# main_board.net
KiCad netlist of a schematic drawn in EAGLE
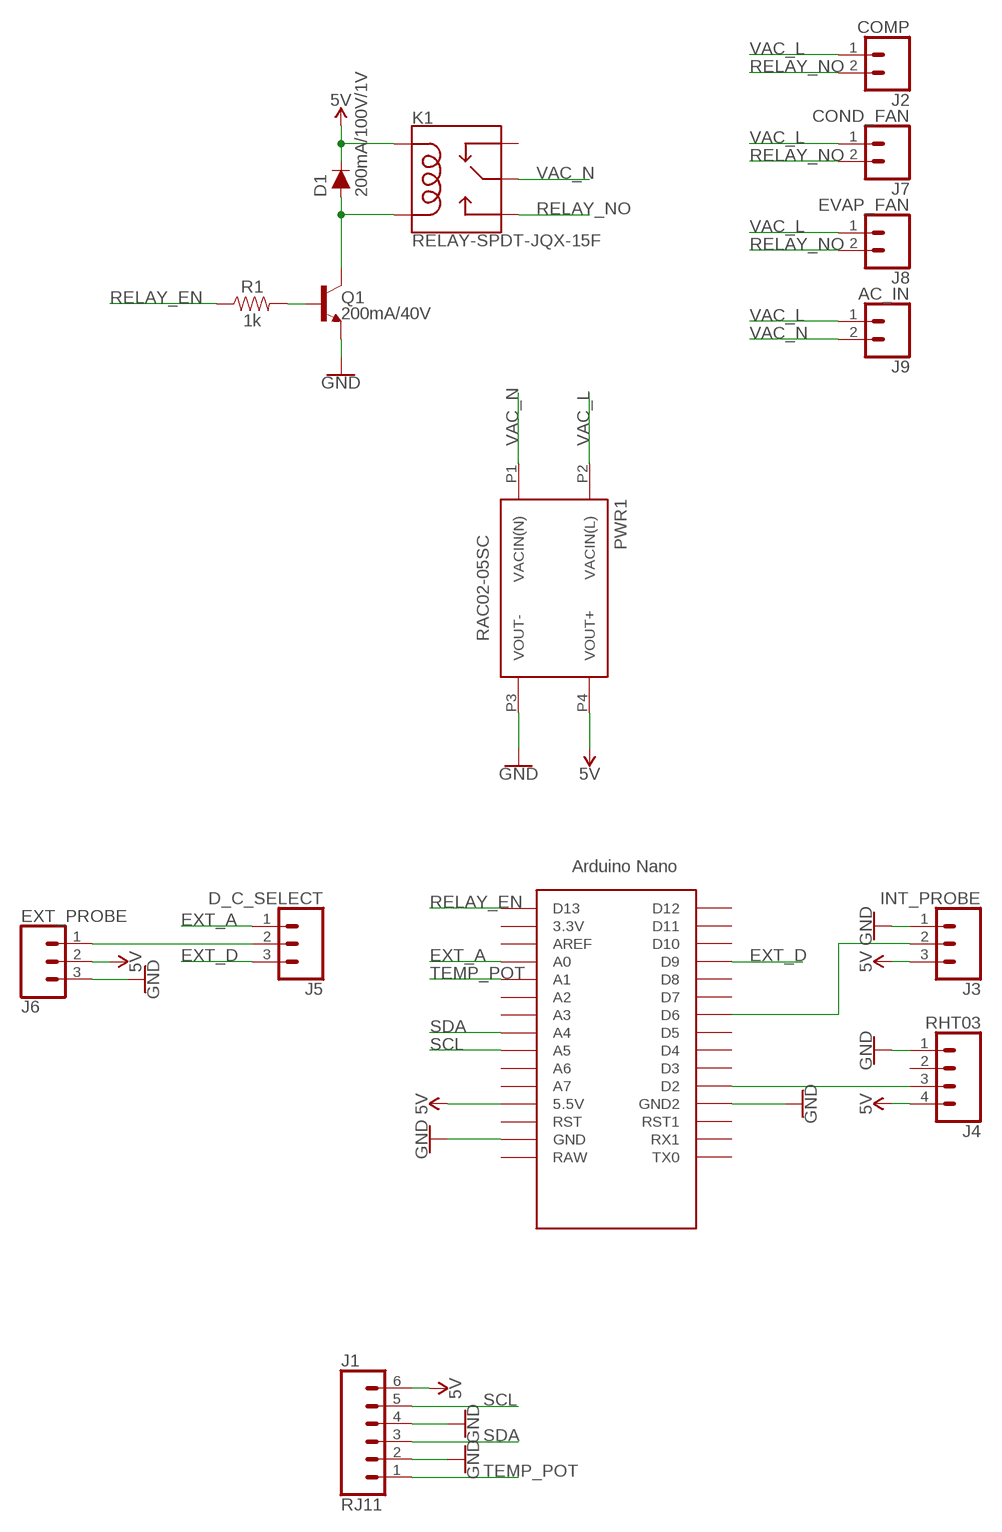
[diagram p0: schematic, sheet 1]

(export (version "E")
  (design (tool "Eeschema 10.0.6"))
  (components
    (comp (ref "D1")
      (value "200mA/100V/1V")
      (footprint "eagle-import:DIODE-1N4148")
      (libsource (lib "eagle-import") (part "DIODE-1N4148"))
    )
    (comp (ref "J1")
      (value "RJ11")
      (footprint "eagle-import:RJ11-6")
      (libsource (lib "eagle-import") (part "RJ11-6"))
    )
    (comp (ref "J2")
      (value "COMP")
      (footprint "eagle-import:SCREWTERMINAL-5MM-2")
      (libsource (lib "eagle-import") (part "CONN_025MM"))
    )
    (comp (ref "J3")
      (value "INT_PROBE")
      (footprint "eagle-import:1X03")
      (libsource (lib "eagle-import") (part "CONN_03"))
    )
    (comp (ref "J4")
      (value "RHT03")
      (footprint "eagle-import:1X04")
      (libsource (lib "eagle-import") (part "CONN_04"))
    )
    (comp (ref "J5")
      (value "D_C_SELECT")
      (footprint "eagle-import:1X03")
      (libsource (lib "eagle-import") (part "CONN_03"))
    )
    (comp (ref "J6")
      (value "EXT_PROBE")
      (footprint "eagle-import:1X03")
      (libsource (lib "eagle-import") (part "CONN_03"))
    )
    (comp (ref "J7")
      (value "COND_FAN")
      (footprint "eagle-import:SCREWTERMINAL-5MM-2")
      (libsource (lib "eagle-import") (part "CONN_025MM"))
    )
    (comp (ref "J8")
      (value "EVAP_FAN")
      (footprint "eagle-import:SCREWTERMINAL-5MM-2")
      (libsource (lib "eagle-import") (part "CONN_025MM"))
    )
    (comp (ref "J9")
      (value "AC_IN")
      (footprint "eagle-import:SCREWTERMINAL-5MM-2")
      (libsource (lib "eagle-import") (part "CONN_025MM"))
    )
    (comp (ref "K1")
      (value "RELAY-SPDT-JQX-15F")
      (footprint "eagle-import:RELAY-T90")
      (libsource (lib "eagle-import") (part "RELAY-SPDT-JQX-15F"))
    )
    (comp (ref "PWR1")
      (value "RAC02-05SC")
      (footprint "eagle-import:LOW_PROFILE_POWER_MODULE")
      (libsource (lib "eagle-import") (part "RACSC02-05"))
    )
    (comp (ref "Q1")
      (value "200mA/40V")
      (footprint "eagle-import:TO-92")
      (libsource (lib "eagle-import") (part "TRANS_NPN-2N3904"))
    )
    (comp (ref "R1")
      (value "1k")
      (footprint "eagle-import:AXIAL-0.3")
      (libsource (lib "eagle-import") (part "1KOHM-HORIZ-1/4W-1%"))
    )
    (comp (ref "U$1")
      (value "NANO")
      (footprint "eagle-import:NANO")
      (libsource (lib "eagle-import") (part "NANO"))
    )
  )
  (nets
    (net (code "1") (name "/EXT_A") (class "Default")
      (node (ref "J5") (pin "1") (pinfunction "1_1") (pintype "passive"))
      (node (ref "U$1") (pin "A0") (pinfunction "A0_A0") (pintype "bidirectional"))
    )
    (net (code "2") (name "/EXT_D") (class "Default")
      (node (ref "J5") (pin "3") (pinfunction "3_3") (pintype "passive"))
      (node (ref "U$1") (pin "D9") (pinfunction "D9_D9") (pintype "bidirectional"))
    )
    (net (code "3") (name "/RELAY_EN") (class "Default")
      (node (ref "R1") (pin "P$1") (pinfunction "1_P$1") (pintype "passive"))
      (node (ref "U$1") (pin "D13") (pinfunction "D13_D13") (pintype "bidirectional"))
    )
    (net (code "4") (name "/RELAY_NO") (class "Default")
      (node (ref "J2") (pin "2") (pinfunction "2_2") (pintype "passive"))
      (node (ref "J7") (pin "2") (pinfunction "2_2") (pintype "passive"))
      (node (ref "J8") (pin "2") (pinfunction "2_2") (pintype "passive"))
      (node (ref "K1") (pin "NO") (pinfunction "NO_NO") (pintype "bidirectional"))
    )
    (net (code "5") (name "/SCL") (class "Default")
      (node (ref "J1") (pin "5") (pinfunction "5_5") (pintype "passive"))
      (node (ref "U$1") (pin "A5") (pinfunction "A5_A5") (pintype "bidirectional"))
    )
    (net (code "6") (name "/SDA") (class "Default")
      (node (ref "J1") (pin "3") (pinfunction "3_3") (pintype "passive"))
      (node (ref "U$1") (pin "A4") (pinfunction "A4_A4") (pintype "bidirectional"))
    )
    (net (code "7") (name "/TEMP_POT") (class "Default")
      (node (ref "J1") (pin "1") (pinfunction "1_1") (pintype "passive"))
      (node (ref "U$1") (pin "A1") (pinfunction "A1_A1") (pintype "bidirectional"))
    )
    (net (code "8") (name "/VAC_L") (class "Default")
      (node (ref "J2") (pin "1") (pinfunction "1_1") (pintype "passive"))
      (node (ref "J7") (pin "1") (pinfunction "1_1") (pintype "passive"))
      (node (ref "J8") (pin "1") (pinfunction "1_1") (pintype "passive"))
      (node (ref "J9") (pin "1") (pinfunction "1_1") (pintype "passive"))
      (node (ref "PWR1") (pin "P2") (pinfunction "VACIN(L)_P2") (pintype "power_in"))
    )
    (net (code "9") (name "/VAC_N") (class "Default")
      (node (ref "J9") (pin "2") (pinfunction "2_2") (pintype "passive"))
      (node (ref "K1") (pin "MAIN") (pinfunction "MAIN_MAIN") (pintype "bidirectional"))
      (node (ref "PWR1") (pin "P1") (pinfunction "VACIN(N)_P1") (pintype "power_in"))
    )
    (net (code "10") (name "5V") (class "Default")
      (node (ref "D1") (pin "C") (pinfunction "C_C") (pintype "passive"))
      (node (ref "J1") (pin "6") (pinfunction "6_6") (pintype "passive"))
      (node (ref "J3") (pin "3") (pinfunction "3_3") (pintype "passive"))
      (node (ref "J4") (pin "4") (pinfunction "4_4") (pintype "passive"))
      (node (ref "J6") (pin "2") (pinfunction "2_2") (pintype "passive"))
      (node (ref "K1") (pin "COIL1") (pinfunction "COIL1_COIL1") (pintype "bidirectional"))
      (node (ref "PWR1") (pin "P4") (pinfunction "VOUT+_P4") (pintype "power_in"))
      (node (ref "U$1") (pin "5V") (pinfunction "5.5V_5V") (pintype "bidirectional"))
    )
    (net (code "11") (name "GND") (class "Default")
      (node (ref "J1") (pin "2") (pinfunction "2_2") (pintype "passive"))
      (node (ref "J1") (pin "4") (pinfunction "4_4") (pintype "passive"))
      (node (ref "J3") (pin "1") (pinfunction "1_1") (pintype "passive"))
      (node (ref "J4") (pin "1") (pinfunction "1_1") (pintype "passive"))
      (node (ref "J6") (pin "3") (pinfunction "3_3") (pintype "passive"))
      (node (ref "PWR1") (pin "P3") (pinfunction "VOUT-_P3") (pintype "power_in"))
      (node (ref "Q1") (pin "1") (pinfunction "E_1") (pintype "passive"))
      (node (ref "U$1") (pin "GND") (pinfunction "GND_GND") (pintype "bidirectional"))
      (node (ref "U$1") (pin "GND1") (pinfunction "GND2_GND1") (pintype "bidirectional"))
    )
    (net (code "12") (name "Net-(J3-Pad2)") (class "Default")
      (node (ref "J3") (pin "2") (pinfunction "2_2") (pintype "passive"))
      (node (ref "U$1") (pin "D6") (pinfunction "D6_D6") (pintype "bidirectional"))
    )
    (net (code "13") (name "Net-(J4-Pad3)") (class "Default")
      (node (ref "J4") (pin "3") (pinfunction "3_3") (pintype "passive"))
      (node (ref "U$1") (pin "D2") (pinfunction "D2_D2") (pintype "bidirectional"))
    )
    (net (code "14") (name "Net-(J5-Pad2)") (class "Default")
      (node (ref "J5") (pin "2") (pinfunction "2_2") (pintype "passive"))
      (node (ref "J6") (pin "1") (pinfunction "1_1") (pintype "passive"))
    )
    (net (code "15") (name "Net-(Q1-B)") (class "Default")
      (node (ref "Q1") (pin "2") (pinfunction "B_2") (pintype "passive"))
      (node (ref "R1") (pin "P$2") (pinfunction "2_P$2") (pintype "passive"))
    )
    (net (code "16") (name "Net-(Q1-C)") (class "Default")
      (node (ref "D1") (pin "A") (pinfunction "A_A") (pintype "passive"))
      (node (ref "K1") (pin "COIL2") (pinfunction "COIL2_COIL2") (pintype "bidirectional"))
      (node (ref "Q1") (pin "3") (pinfunction "C_3") (pintype "passive"))
    )
    (net (code "17") (name "unconnected-(J4-Pad2)") (class "Default")
      (node (ref "J4") (pin "2") (pinfunction "2_2") (pintype "passive"))
    )
    (net (code "18") (name "unconnected-(K1-PadNC)") (class "Default")
      (node (ref "K1") (pin "NC") (pinfunction "NC_NC") (pintype "bidirectional"))
    )
    (net (code "19") (name "unconnected-(U$1-Pad3.3V)") (class "Default")
      (node (ref "U$1") (pin "3.3V") (pinfunction "3.3V_3.3V") (pintype "bidirectional"))
    )
    (net (code "20") (name "unconnected-(U$1-PadA2)") (class "Default")
      (node (ref "U$1") (pin "A2") (pinfunction "A2_A2") (pintype "bidirectional"))
    )
    (net (code "21") (name "unconnected-(U$1-PadA3)") (class "Default")
      (node (ref "U$1") (pin "A3") (pinfunction "A3_A3") (pintype "bidirectional"))
    )
    (net (code "22") (name "unconnected-(U$1-PadA6)") (class "Default")
      (node (ref "U$1") (pin "A6") (pinfunction "A6_A6") (pintype "bidirectional"))
    )
    (net (code "23") (name "unconnected-(U$1-PadA7)") (class "Default")
      (node (ref "U$1") (pin "A7") (pinfunction "A7_A7") (pintype "bidirectional"))
    )
    (net (code "24") (name "unconnected-(U$1-PadAREF)") (class "Default")
      (node (ref "U$1") (pin "AREF") (pinfunction "AREF_AREF") (pintype "bidirectional"))
    )
    (net (code "25") (name "unconnected-(U$1-PadD3)") (class "Default")
      (node (ref "U$1") (pin "D3") (pinfunction "D3_D3") (pintype "bidirectional"))
    )
    (net (code "26") (name "unconnected-(U$1-PadD4)") (class "Default")
      (node (ref "U$1") (pin "D4") (pinfunction "D4_D4") (pintype "bidirectional"))
    )
    (net (code "27") (name "unconnected-(U$1-PadD5)") (class "Default")
      (node (ref "U$1") (pin "D5") (pinfunction "D5_D5") (pintype "bidirectional"))
    )
    (net (code "28") (name "unconnected-(U$1-PadD7)") (class "Default")
      (node (ref "U$1") (pin "D7") (pinfunction "D7_D7") (pintype "bidirectional"))
    )
    (net (code "29") (name "unconnected-(U$1-PadD8)") (class "Default")
      (node (ref "U$1") (pin "D8") (pinfunction "D8_D8") (pintype "bidirectional"))
    )
    (net (code "30") (name "unconnected-(U$1-PadD10)") (class "Default")
      (node (ref "U$1") (pin "D10") (pinfunction "D10_D10") (pintype "bidirectional"))
    )
    (net (code "31") (name "unconnected-(U$1-PadD11)") (class "Default")
      (node (ref "U$1") (pin "D11") (pinfunction "D11_D11") (pintype "bidirectional"))
    )
    (net (code "32") (name "unconnected-(U$1-PadD12)") (class "Default")
      (node (ref "U$1") (pin "D12") (pinfunction "D12_D12") (pintype "bidirectional"))
    )
    (net (code "33") (name "unconnected-(U$1-PadICSP1)") (class "Default")
      (node (ref "U$1") (pin "ICSP1") (pinfunction "ICSP1_ICSP1") (pintype "bidirectional"))
    )
    (net (code "34") (name "unconnected-(U$1-PadICSP2)") (class "Default")
      (node (ref "U$1") (pin "ICSP2") (pinfunction "ICSP2_ICSP2") (pintype "bidirectional"))
    )
    (net (code "35") (name "unconnected-(U$1-PadICSP3)") (class "Default")
      (node (ref "U$1") (pin "ICSP3") (pinfunction "ICSP3_ICSP3") (pintype "bidirectional"))
    )
    (net (code "36") (name "unconnected-(U$1-PadICSP4)") (class "Default")
      (node (ref "U$1") (pin "ICSP4") (pinfunction "ICSP4_ICSP4") (pintype "bidirectional"))
    )
    (net (code "37") (name "unconnected-(U$1-PadICSP5)") (class "Default")
      (node (ref "U$1") (pin "ICSP5") (pinfunction "ICSP5_ICSP5") (pintype "bidirectional"))
    )
    (net (code "38") (name "unconnected-(U$1-PadICSP6)") (class "Default")
      (node (ref "U$1") (pin "ICSP6") (pinfunction "ICSP6_ICSP6") (pintype "bidirectional"))
    )
    (net (code "39") (name "unconnected-(U$1-PadRAW)") (class "Default")
      (node (ref "U$1") (pin "RAW") (pinfunction "RAW_RAW") (pintype "bidirectional"))
    )
    (net (code "40") (name "unconnected-(U$1-PadRST)") (class "Default")
      (node (ref "U$1") (pin "RST") (pinfunction "RST_RST") (pintype "bidirectional"))
    )
    (net (code "41") (name "unconnected-(U$1-PadRST1)") (class "Default")
      (node (ref "U$1") (pin "RST1") (pinfunction "RST1_RST1") (pintype "bidirectional"))
    )
    (net (code "42") (name "unconnected-(U$1-PadRX1)") (class "Default")
      (node (ref "U$1") (pin "RX1") (pinfunction "RX1_RX1") (pintype "bidirectional"))
    )
    (net (code "43") (name "unconnected-(U$1-PadTX0)") (class "Default")
      (node (ref "U$1") (pin "TX0") (pinfunction "TX0_TX0") (pintype "bidirectional"))
    )
  )
)
